# takiuino-m18-smashed-routed.net
KiCad netlist of a schematic drawn in EAGLE
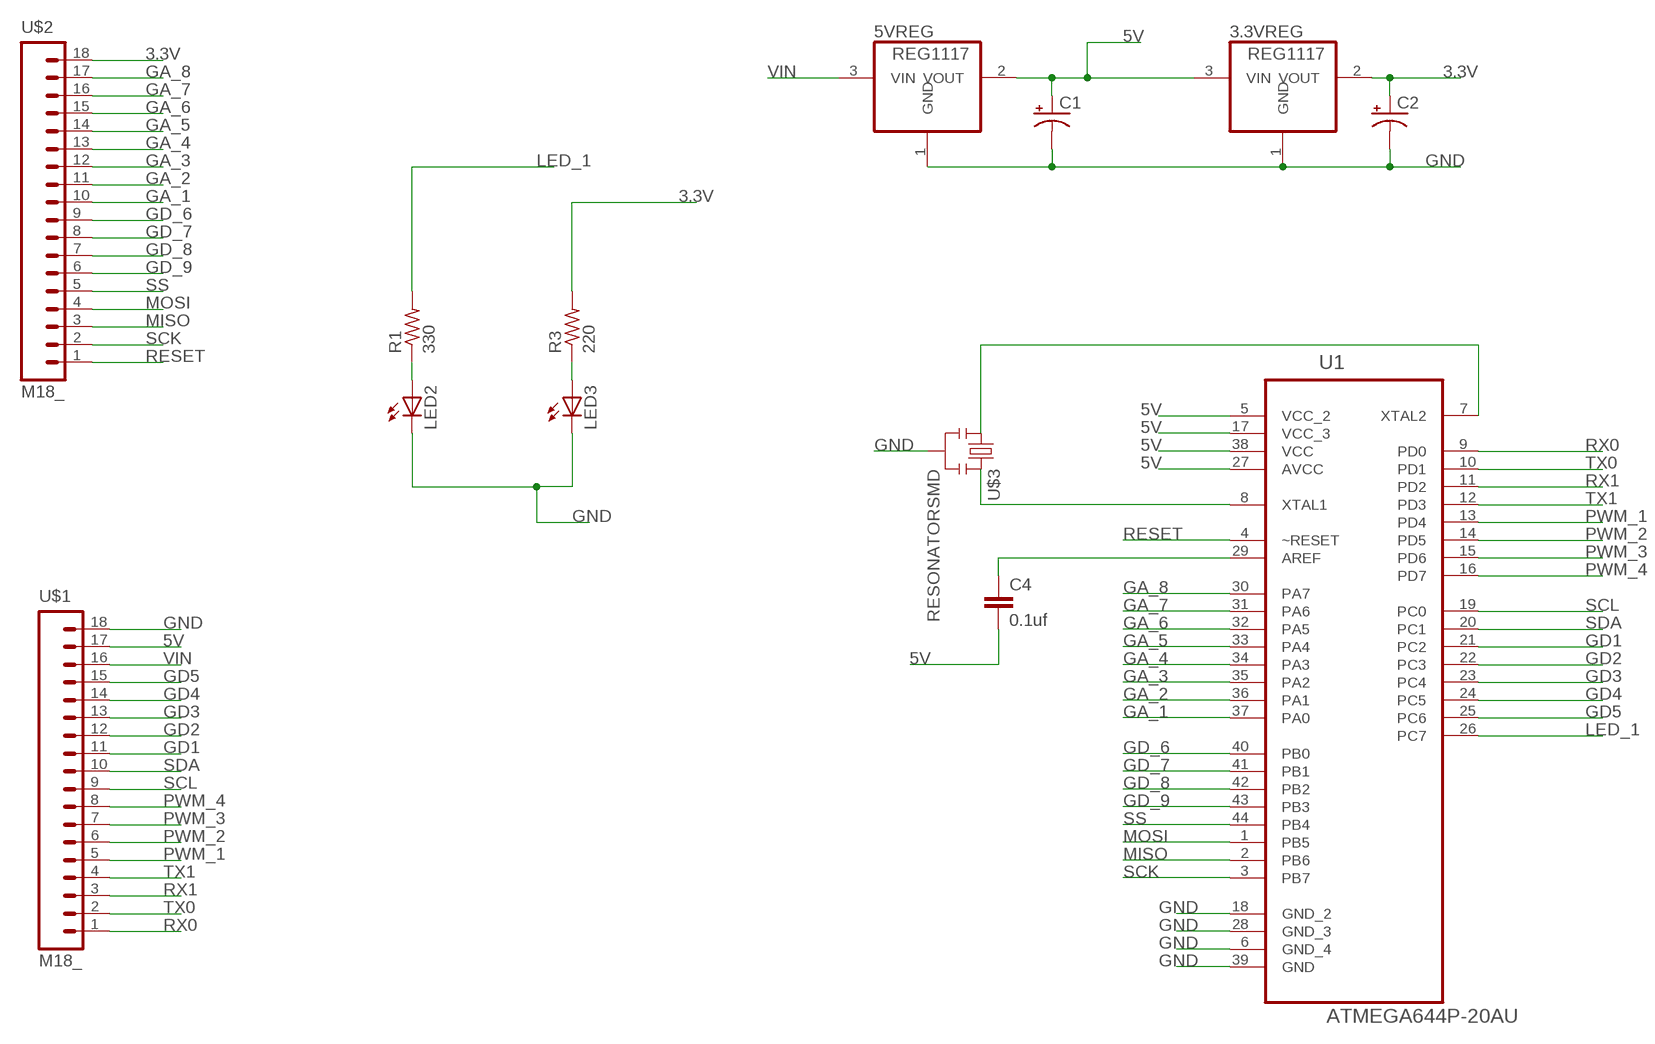
[diagram p0: schematic, sheet 1]

(export (version "E")
  (design (tool "Eeschema 10.0.6"))
  (components
    (comp (ref "3.3VREG")
      (value "REG1117")
      (footprint "eagle-import:SOT223")
      (libsource (lib "eagle-import") (part "REG1117"))
    )
    (comp (ref "5VREG")
      (value "REG1117")
      (footprint "eagle-import:SOT223")
      (libsource (lib "eagle-import") (part "REG1117"))
    )
    (comp (ref "C1")
      (value "CAP_POL1206")
      (footprint "eagle-import:EIA3216")
      (libsource (lib "eagle-import") (part "CAP_POL1206"))
    )
    (comp (ref "C2")
      (value "CAP_POL1206")
      (footprint "eagle-import:EIA3216")
      (libsource (lib "eagle-import") (part "CAP_POL1206"))
    )
    (comp (ref "C4")
      (value "0.1uf")
      (footprint "eagle-import:0603-CAP")
      (libsource (lib "eagle-import") (part "CAP0603-CAP"))
    )
    (comp (ref "LED2")
      (value "LEDCHIP-LED0603")
      (footprint "eagle-import:CHIP-LED0603")
      (libsource (lib "eagle-import") (part "LEDCHIP-LED0603"))
    )
    (comp (ref "LED3")
      (value "LEDCHIP-LED0603")
      (footprint "eagle-import:CHIP-LED0603")
      (libsource (lib "eagle-import") (part "LEDCHIP-LED0603"))
    )
    (comp (ref "R1")
      (value "330")
      (footprint "eagle-import:R0603")
      (libsource (lib "eagle-import") (part "R-US_R0603"))
    )
    (comp (ref "R3")
      (value "220")
      (footprint "eagle-import:R0603")
      (libsource (lib "eagle-import") (part "R-US_R0603"))
    )
    (comp (ref "U$1")
      (value "M18_")
      (footprint "eagle-import:1X18")
      (libsource (lib "eagle-import") (part "M18_"))
    )
    (comp (ref "U$2")
      (value "M18_")
      (footprint "eagle-import:1X18")
      (libsource (lib "eagle-import") (part "M18_"))
    )
    (comp (ref "U$3")
      (value "RESONATORSMD")
      (footprint "eagle-import:RESONATOR-SMD")
      (libsource (lib "eagle-import") (part "RESONATORSMD"))
    )
    (comp (ref "U1")
      (value "ATMEGA644P-20AU")
      (footprint "eagle-import:QFP80P1200X1200X120-44N")
      (libsource (lib "eagle-import") (part "ATMEGA644P-20AU"))
    )
  )
  (nets
    (net (code "1") (name "/3.3V") (class "Default")
      (node (ref "3.3VREG") (pin "2") (pinfunction "VOUT_2") (pintype "output"))
      (node (ref "C2") (pin "A") (pinfunction "+_A") (pintype "passive"))
      (node (ref "R3") (pin "2") (pinfunction "2_2") (pintype "passive"))
      (node (ref "U$2") (pin "18") (pinfunction "18_18") (pintype "passive"))
    )
    (net (code "2") (name "/5V") (class "Default")
      (node (ref "3.3VREG") (pin "3") (pinfunction "VIN_3") (pintype "input"))
      (node (ref "5VREG") (pin "2") (pinfunction "VOUT_2") (pintype "output"))
      (node (ref "C1") (pin "A") (pinfunction "+_A") (pintype "passive"))
      (node (ref "C4") (pin "2") (pinfunction "2_2") (pintype "passive"))
      (node (ref "U$1") (pin "17") (pinfunction "17_17") (pintype "passive"))
      (node (ref "U1") (pin "17") (pinfunction "VCC_3_17") (pintype "power_in"))
      (node (ref "U1") (pin "27") (pinfunction "AVCC_27") (pintype "power_in"))
      (node (ref "U1") (pin "38") (pinfunction "VCC_38") (pintype "power_in"))
      (node (ref "U1") (pin "5") (pinfunction "VCC_2_5") (pintype "power_in"))
    )
    (net (code "3") (name "/GA_1") (class "Default")
      (node (ref "U$2") (pin "10") (pinfunction "10_10") (pintype "passive"))
      (node (ref "U1") (pin "37") (pinfunction "PA0_37") (pintype "bidirectional"))
    )
    (net (code "4") (name "/GA_2") (class "Default")
      (node (ref "U$2") (pin "11") (pinfunction "11_11") (pintype "passive"))
      (node (ref "U1") (pin "36") (pinfunction "PA1_36") (pintype "bidirectional"))
    )
    (net (code "5") (name "/GA_3") (class "Default")
      (node (ref "U$2") (pin "12") (pinfunction "12_12") (pintype "passive"))
      (node (ref "U1") (pin "35") (pinfunction "PA2_35") (pintype "bidirectional"))
    )
    (net (code "6") (name "/GA_4") (class "Default")
      (node (ref "U$2") (pin "13") (pinfunction "13_13") (pintype "passive"))
      (node (ref "U1") (pin "34") (pinfunction "PA3_34") (pintype "bidirectional"))
    )
    (net (code "7") (name "/GA_5") (class "Default")
      (node (ref "U$2") (pin "14") (pinfunction "14_14") (pintype "passive"))
      (node (ref "U1") (pin "33") (pinfunction "PA4_33") (pintype "bidirectional"))
    )
    (net (code "8") (name "/GA_6") (class "Default")
      (node (ref "U$2") (pin "15") (pinfunction "15_15") (pintype "passive"))
      (node (ref "U1") (pin "32") (pinfunction "PA5_32") (pintype "bidirectional"))
    )
    (net (code "9") (name "/GA_7") (class "Default")
      (node (ref "U$2") (pin "16") (pinfunction "16_16") (pintype "passive"))
      (node (ref "U1") (pin "31") (pinfunction "PA6_31") (pintype "bidirectional"))
    )
    (net (code "10") (name "/GA_8") (class "Default")
      (node (ref "U$2") (pin "17") (pinfunction "17_17") (pintype "passive"))
      (node (ref "U1") (pin "30") (pinfunction "PA7_30") (pintype "bidirectional"))
    )
    (net (code "11") (name "/GD1") (class "Default")
      (node (ref "U$1") (pin "11") (pinfunction "11_11") (pintype "passive"))
      (node (ref "U1") (pin "21") (pinfunction "PC2_21") (pintype "bidirectional"))
    )
    (net (code "12") (name "/GD2") (class "Default")
      (node (ref "U$1") (pin "12") (pinfunction "12_12") (pintype "passive"))
      (node (ref "U1") (pin "22") (pinfunction "PC3_22") (pintype "bidirectional"))
    )
    (net (code "13") (name "/GD3") (class "Default")
      (node (ref "U$1") (pin "13") (pinfunction "13_13") (pintype "passive"))
      (node (ref "U1") (pin "23") (pinfunction "PC4_23") (pintype "bidirectional"))
    )
    (net (code "14") (name "/GD4") (class "Default")
      (node (ref "U$1") (pin "14") (pinfunction "14_14") (pintype "passive"))
      (node (ref "U1") (pin "24") (pinfunction "PC5_24") (pintype "bidirectional"))
    )
    (net (code "15") (name "/GD5") (class "Default")
      (node (ref "U$1") (pin "15") (pinfunction "15_15") (pintype "passive"))
      (node (ref "U1") (pin "25") (pinfunction "PC6_25") (pintype "bidirectional"))
    )
    (net (code "16") (name "/GD_6") (class "Default")
      (node (ref "U$2") (pin "9") (pinfunction "9_9") (pintype "passive"))
      (node (ref "U1") (pin "40") (pinfunction "PB0_40") (pintype "bidirectional"))
    )
    (net (code "17") (name "/GD_7") (class "Default")
      (node (ref "U$2") (pin "8") (pinfunction "8_8") (pintype "passive"))
      (node (ref "U1") (pin "41") (pinfunction "PB1_41") (pintype "bidirectional"))
    )
    (net (code "18") (name "/GD_8") (class "Default")
      (node (ref "U$2") (pin "7") (pinfunction "7_7") (pintype "passive"))
      (node (ref "U1") (pin "42") (pinfunction "PB2_42") (pintype "bidirectional"))
    )
    (net (code "19") (name "/GD_9") (class "Default")
      (node (ref "U$2") (pin "6") (pinfunction "6_6") (pintype "passive"))
      (node (ref "U1") (pin "43") (pinfunction "PB3_43") (pintype "bidirectional"))
    )
    (net (code "20") (name "/GND") (class "Default")
      (node (ref "3.3VREG") (pin "1") (pinfunction "GND_1") (pintype "power_in"))
      (node (ref "5VREG") (pin "1") (pinfunction "GND_1") (pintype "power_in"))
      (node (ref "C1") (pin "C") (pinfunction "-_C") (pintype "passive"))
      (node (ref "C2") (pin "C") (pinfunction "-_C") (pintype "passive"))
      (node (ref "LED2") (pin "C") (pinfunction "C_C") (pintype "passive"))
      (node (ref "LED3") (pin "C") (pinfunction "C_C") (pintype "passive"))
      (node (ref "U$1") (pin "18") (pinfunction "18_18") (pintype "passive"))
      (node (ref "U$3") (pin "2") (pinfunction "2_2") (pintype "passive"))
      (node (ref "U1") (pin "18") (pinfunction "GND_2_18") (pintype "passive"))
      (node (ref "U1") (pin "28") (pinfunction "GND_3_28") (pintype "passive"))
      (node (ref "U1") (pin "39") (pinfunction "GND_39") (pintype "passive"))
      (node (ref "U1") (pin "6") (pinfunction "GND_4_6") (pintype "passive"))
    )
    (net (code "21") (name "/LED_1") (class "Default")
      (node (ref "R1") (pin "2") (pinfunction "2_2") (pintype "passive"))
      (node (ref "U1") (pin "26") (pinfunction "PC7_26") (pintype "bidirectional"))
    )
    (net (code "22") (name "/MISO") (class "Default")
      (node (ref "U$2") (pin "3") (pinfunction "3_3") (pintype "passive"))
      (node (ref "U1") (pin "2") (pinfunction "PB6_2") (pintype "bidirectional"))
    )
    (net (code "23") (name "/MOSI") (class "Default")
      (node (ref "U$2") (pin "4") (pinfunction "4_4") (pintype "passive"))
      (node (ref "U1") (pin "1") (pinfunction "PB5_1") (pintype "bidirectional"))
    )
    (net (code "24") (name "/PWM_1") (class "Default")
      (node (ref "U$1") (pin "5") (pinfunction "5_5") (pintype "passive"))
      (node (ref "U1") (pin "13") (pinfunction "PD4_13") (pintype "bidirectional"))
    )
    (net (code "25") (name "/PWM_2") (class "Default")
      (node (ref "U$1") (pin "6") (pinfunction "6_6") (pintype "passive"))
      (node (ref "U1") (pin "14") (pinfunction "PD5_14") (pintype "bidirectional"))
    )
    (net (code "26") (name "/PWM_3") (class "Default")
      (node (ref "U$1") (pin "7") (pinfunction "7_7") (pintype "passive"))
      (node (ref "U1") (pin "15") (pinfunction "PD6_15") (pintype "bidirectional"))
    )
    (net (code "27") (name "/PWM_4") (class "Default")
      (node (ref "U$1") (pin "8") (pinfunction "8_8") (pintype "passive"))
      (node (ref "U1") (pin "16") (pinfunction "PD7_16") (pintype "bidirectional"))
    )
    (net (code "28") (name "/RESET") (class "Default")
      (node (ref "U$2") (pin "1") (pinfunction "1_1") (pintype "passive"))
      (node (ref "U1") (pin "4") (pinfunction "~{RESET}_4") (pintype "input"))
    )
    (net (code "29") (name "/RX0") (class "Default")
      (node (ref "U$1") (pin "1") (pinfunction "1_1") (pintype "passive"))
      (node (ref "U1") (pin "9") (pinfunction "PD0_9") (pintype "bidirectional"))
    )
    (net (code "30") (name "/RX1") (class "Default")
      (node (ref "U$1") (pin "3") (pinfunction "3_3") (pintype "passive"))
      (node (ref "U1") (pin "11") (pinfunction "PD2_11") (pintype "bidirectional"))
    )
    (net (code "31") (name "/SCK") (class "Default")
      (node (ref "U$2") (pin "2") (pinfunction "2_2") (pintype "passive"))
      (node (ref "U1") (pin "3") (pinfunction "PB7_3") (pintype "bidirectional"))
    )
    (net (code "32") (name "/SCL") (class "Default")
      (node (ref "U$1") (pin "9") (pinfunction "9_9") (pintype "passive"))
      (node (ref "U1") (pin "19") (pinfunction "PC0_19") (pintype "bidirectional"))
    )
    (net (code "33") (name "/SDA") (class "Default")
      (node (ref "U$1") (pin "10") (pinfunction "10_10") (pintype "passive"))
      (node (ref "U1") (pin "20") (pinfunction "PC1_20") (pintype "bidirectional"))
    )
    (net (code "34") (name "/SS") (class "Default")
      (node (ref "U$2") (pin "5") (pinfunction "5_5") (pintype "passive"))
      (node (ref "U1") (pin "44") (pinfunction "PB4_44") (pintype "bidirectional"))
    )
    (net (code "35") (name "/TX0") (class "Default")
      (node (ref "U$1") (pin "2") (pinfunction "2_2") (pintype "passive"))
      (node (ref "U1") (pin "10") (pinfunction "PD1_10") (pintype "bidirectional"))
    )
    (net (code "36") (name "/TX1") (class "Default")
      (node (ref "U$1") (pin "4") (pinfunction "4_4") (pintype "passive"))
      (node (ref "U1") (pin "12") (pinfunction "PD3_12") (pintype "bidirectional"))
    )
    (net (code "37") (name "/VIN") (class "Default")
      (node (ref "5VREG") (pin "3") (pinfunction "VIN_3") (pintype "input"))
      (node (ref "U$1") (pin "16") (pinfunction "16_16") (pintype "passive"))
    )
    (net (code "38") (name "Net-(LED2-PadA)") (class "Default")
      (node (ref "LED2") (pin "A") (pinfunction "A_A") (pintype "passive"))
      (node (ref "R1") (pin "1") (pinfunction "1_1") (pintype "passive"))
    )
    (net (code "39") (name "Net-(LED3-PadA)") (class "Default")
      (node (ref "LED3") (pin "A") (pinfunction "A_A") (pintype "passive"))
      (node (ref "R3") (pin "1") (pinfunction "1_1") (pintype "passive"))
    )
    (net (code "40") (name "Net-(U1-AREF)") (class "Default")
      (node (ref "C4") (pin "1") (pinfunction "1_1") (pintype "passive"))
      (node (ref "U1") (pin "29") (pinfunction "AREF_29") (pintype "input"))
    )
    (net (code "41") (name "Net-(U1-XTAL1)") (class "Default")
      (node (ref "U$3") (pin "3") (pinfunction "3_3") (pintype "passive"))
      (node (ref "U1") (pin "8") (pinfunction "XTAL1_8") (pintype "input"))
    )
    (net (code "42") (name "Net-(U1-XTAL2)") (class "Default")
      (node (ref "U$3") (pin "1") (pinfunction "1_1") (pintype "passive"))
      (node (ref "U1") (pin "7") (pinfunction "XTAL2_7") (pintype "output"))
    )
  )
)
